# xmega.net
KiCad netlist of a schematic drawn in Altium Designer
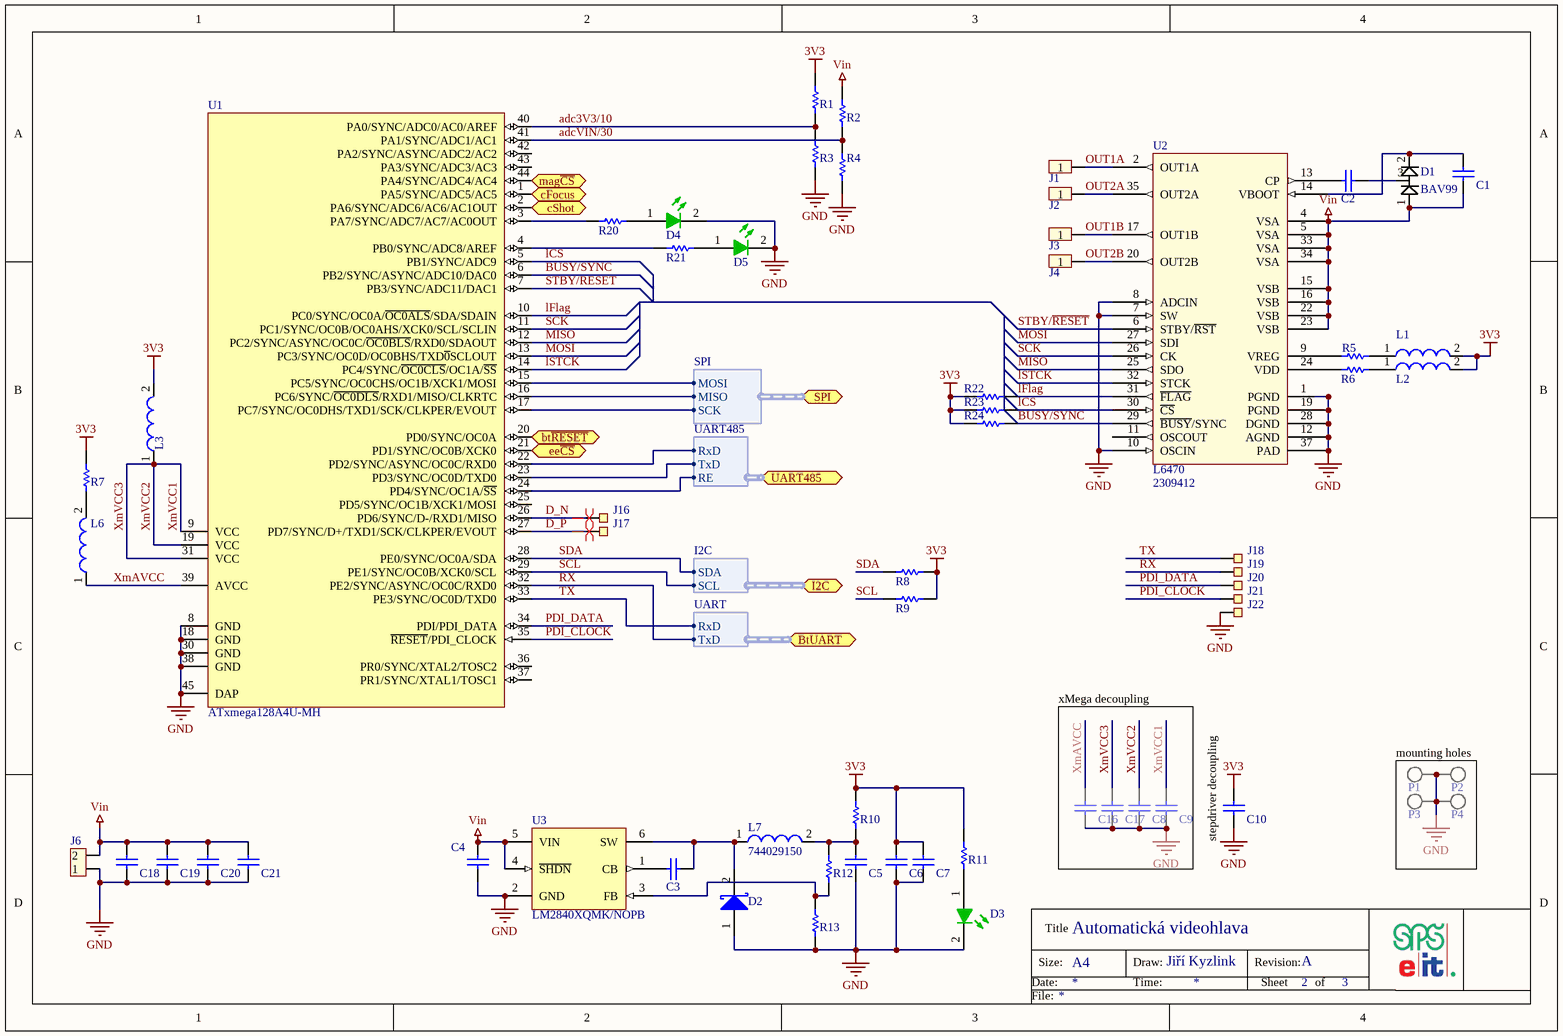
[diagram p0: xmega.SchDoc]

(export (version "E")
  (design (tool "Eeschema 10.0.6"))
  (components
    (comp (ref "C1")
      (value "CAP 220nF 50V 0603(1608)")
      (footprint "CAPC0603(1608)100_L")
      (description "CAP 220nF 50V ±20% 0603 (1608 Metric) Thickness 1mm SMD")
      (fields (field (name "TOLERANCE") "±20%"))
      (libsource (lib "Altium Content Vault") (part "CAP"))
    )
    (comp (ref "C2")
      (value "CAP 10nF 16V 0402(1005)")
      (footprint "CAPC0402(1005)60_L")
      (description "CAP 10nF 16V ±10% 0402 (1005 Metric) Thickness 0.6mm SMD")
      (fields (field (name "TOLERANCE") "±10%"))
      (libsource (lib "Altium Content Vault") (part "CAP"))
    )
    (comp (ref "C3")
      (value "CAP 100nF 16V 0402(1005)")
      (footprint "CAPC0402(1005)60_L")
      (description "CAP 100nF 16V ±10% 0402 (1005 Metric) Thickness 0.6mm SMD")
      (fields (field (name "TOLERANCE") "±10%"))
      (libsource (lib "Altium Content Vault") (part "CMP-1034-02069-1"))
    )
    (comp (ref "C4")
      (value "CAP 2.2pF 50V 0402(1005)")
      (footprint "CAPC0402(1005)60_L")
      (description "CAP 2.2pF 50V ±2% 0402 (1005 Metric) Thickness 0.6mm SMD")
      (fields (field (name "TOLERANCE") "±2%"))
      (libsource (lib "Altium Content Vault") (part "CAP"))
    )
    (comp (ref "C5")
      (value "CAP 10uF 6.3V 0402(1005)")
      (footprint "CAPC0402(1005)60_L")
      (description "CAP 10uF 6.3V ±20% 0402 (1005 Metric) Thickness 0.6mm SMD")
      (fields (field (name "TOLERANCE") "±20%"))
      (libsource (lib "Altium Content Vault") (part "CAP"))
    )
    (comp (ref "C6")
      (value "CAP 10uF 6.3V 0402(1005)")
      (footprint "CAPC0402(1005)60_L")
      (description "CAP 10uF 6.3V ±20% 0402 (1005 Metric) Thickness 0.6mm SMD")
      (fields (field (name "TOLERANCE") "±20%"))
      (libsource (lib "Altium Content Vault") (part "CAP"))
    )
    (comp (ref "C7")
      (value "CAP 10uF 6.3V 0402(1005)")
      (footprint "CAPC0402(1005)60_L")
      (description "CAP 10uF 6.3V ±20% 0402 (1005 Metric) Thickness 0.6mm SMD")
      (fields (field (name "TOLERANCE") "±20%"))
      (libsource (lib "Altium Content Vault") (part "CAP"))
    )
    (comp (ref "C8")
      (value "CAP 100nF 6.3V 0402(1005)")
      (footprint "CAPC0402(1005)60_L")
      (description "CAP 100nF 6.3V ±5% 0402 (1005 Metric) Thickness 0.6mm SMD")
      (fields (field (name "TOLERANCE") "±5%"))
      (libsource (lib "Altium Content Vault") (part "CAP"))
    )
    (comp (ref "C9")
      (value "CAP 100nF 6.3V 0402(1005)")
      (footprint "CAPC0402(1005)60_L")
      (description "CAP 100nF 6.3V ±5% 0402 (1005 Metric) Thickness 0.6mm SMD")
      (fields (field (name "TOLERANCE") "±5%"))
      (libsource (lib "Altium Content Vault") (part "CAP"))
    )
    (comp (ref "C10")
      (value "CAP 100nF 6.3V 0402(1005)")
      (footprint "CAPC0402(1005)60_L")
      (description "CAP 100nF 6.3V ±5% 0402 (1005 Metric) Thickness 0.6mm SMD")
      (fields (field (name "TOLERANCE") "±5%"))
      (libsource (lib "Altium Content Vault") (part "CAP"))
    )
    (comp (ref "C16")
      (value "CAP 100nF 16V 0402(1005)")
      (footprint "CAPC0402(1005)60_L")
      (description "CAP 100nF 16V ±10% 0402 (1005 Metric) Thickness 0.6mm SMD")
      (fields (field (name "TOLERANCE") "±10%"))
      (libsource (lib "Altium Content Vault") (part "CMP-1034-02069-1"))
    )
    (comp (ref "C17")
      (value "CAP 100nF 6.3V 0402(1005)")
      (footprint "CAPC0402(1005)60_L")
      (description "CAP 100nF 6.3V ±5% 0402 (1005 Metric) Thickness 0.6mm SMD")
      (fields (field (name "TOLERANCE") "±5%"))
      (libsource (lib "Altium Content Vault") (part "CAP"))
    )
    (comp (ref "C18")
      (value "CAP 1uF 50V 0603(1608)")
      (footprint "CAPC0603(1608)100_L")
      (description "CAP 1uF 50V ±10% 0603 (1608 Metric) Thickness 1mm SMD")
      (fields (field (name "TOLERANCE") "±10%"))
      (libsource (lib "Altium Content Vault") (part "CAP"))
    )
    (comp (ref "C19")
      (value "CAP 1uF 50V 0603(1608)")
      (footprint "CAPC0603(1608)100_L")
      (description "CAP 1uF 50V ±10% 0603 (1608 Metric) Thickness 1mm SMD")
      (fields (field (name "TOLERANCE") "±10%"))
      (libsource (lib "Altium Content Vault") (part "CAP"))
    )
    (comp (ref "C20")
      (value "CAP 1uF 50V 0603(1608)")
      (footprint "CAPC0603(1608)100_L")
      (description "CAP 1uF 50V ±10% 0603 (1608 Metric) Thickness 1mm SMD")
      (fields (field (name "TOLERANCE") "±10%"))
      (libsource (lib "Altium Content Vault") (part "CAP"))
    )
    (comp (ref "C21")
      (value "CAP 1uF 50V 0603(1608)")
      (footprint "CAPC0603(1608)100_L")
      (description "CAP 1uF 50V ±10% 0603 (1608 Metric) Thickness 1mm SMD")
      (fields (field (name "TOLERANCE") "±10%"))
      (libsource (lib "Altium Content Vault") (part "CAP"))
    )
    (comp (ref "D1")
      (value "BAV99")
      (footprint "MCHP-SOT-23-NB3_N")
      (libsource (lib "mojeLib") (part "BAV99"))
    )
    (comp (ref "D2")
      (value "ZHCS400")
      (footprint "DIOD-SOD323-2_V")
      (description "Schottky Diode, 400mA")
      (fields (field (name "MANUFACTURER") "Diodes Inc"))
      (libsource (lib "Altium Content Vault") (part "DIOD-DSKY-A1K2-2"))
    )
    (comp (ref "D3")
      (value "KP-1608MGC")
      (footprint "KING-0603LED_GREEN_V")
      (description "LED, SMT, 0603(1608), 1.1mm thickness, Green")
      (fields (field (name "MANUFACTURER") "Kingbright"))
      (libsource (lib "Altium Content Vault") (part "CMP-0404-00001-1"))
    )
    (comp (ref "D4")
      (value "KP-1608MGC")
      (footprint "KING-0603LED_GREEN_V")
      (description "LED, SMT, 0603(1608), 1.1mm thickness, Green")
      (fields (field (name "MANUFACTURER") "Kingbright"))
      (libsource (lib "Altium Content Vault") (part "CMP-0404-00001-1"))
    )
    (comp (ref "D5")
      (value "KP-1608MGC")
      (footprint "KING-0603LED_GREEN_V")
      (description "LED, SMT, 0603(1608), 1.1mm thickness, Green")
      (fields (field (name "MANUFACTURER") "Kingbright"))
      (libsource (lib "Altium Content Vault") (part "CMP-0404-00001-1"))
    )
    (comp (ref "J1") (value "Pin") (footprint "Hole 1mm") (libsource (lib "mojeLib") (part "Pin")))
    (comp (ref "J2") (value "Pin") (footprint "Hole 1mm") (libsource (lib "mojeLib") (part "Pin")))
    (comp (ref "J3") (value "Pin") (footprint "Hole 1mm") (libsource (lib "mojeLib") (part "Pin")))
    (comp (ref "J4") (value "Pin") (footprint "Hole 1mm") (libsource (lib "mojeLib") (part "Pin")))
    (comp (ref "J6")
      (value "jumper")
      (footprint "header 2pin")
      (libsource (lib "mojeLib") (part "header 2pin"))
    )
    (comp (ref "J16") (value "smd pad") (footprint "pad 0.75x1.5mm") (libsource (lib "mojeLib") (part "pad")))
    (comp (ref "J17") (value "smd pad") (footprint "pad 0.75x1.5mm") (libsource (lib "mojeLib") (part "pad")))
    (comp (ref "J18") (value "smd pad") (footprint "pad 0.75x1.5mm") (libsource (lib "mojeLib") (part "pad")))
    (comp (ref "J19") (value "smd pad") (footprint "pad 0.75x1.5mm") (libsource (lib "mojeLib") (part "pad")))
    (comp (ref "J20") (value "smd pad") (footprint "pad 0.75x1.5mm") (libsource (lib "mojeLib") (part "pad")))
    (comp (ref "J21") (value "smd pad") (footprint "pad 0.75x1.5mm") (libsource (lib "mojeLib") (part "pad")))
    (comp (ref "J22") (value "smd pad") (footprint "pad 0.75x1.5mm") (libsource (lib "mojeLib") (part "pad")))
    (comp (ref "L1")
      (value "742843122")
      (footprint "0402")
      (description "SMD EMI Suppression Ferrite Bead WE-CBF HF, Z = 220 Ohm")
      (libsource (lib "Altium Content Vault") (part "CMP-0220-00130-1"))
    )
    (comp (ref "L2")
      (value "742843122")
      (footprint "0402")
      (description "SMD EMI Suppression Ferrite Bead WE-CBF HF, Z = 220 Ohm")
      (libsource (lib "Altium Content Vault") (part "CMP-0220-00130-1"))
    )
    (comp (ref "L3")
      (value "742843122")
      (footprint "0402")
      (description "SMD EMI Suppression Ferrite Bead WE-CBF HF, Z = 220 Ohm")
      (libsource (lib "Altium Content Vault") (part "CMP-0220-00130-1"))
    )
    (comp (ref "L6")
      (value "742843122")
      (footprint "0402")
      (description "SMD EMI Suppression Ferrite Bead WE-CBF HF, Z = 220 Ohm")
      (libsource (lib "Altium Content Vault") (part "CMP-0220-00130-1"))
    )
    (comp (ref "L7")
      (value "744029150")
      (footprint "WE-TPC-2813-TH")
      (description "SMD Shielded Tiny Power Inductor WE-TPC, L = 15.0 µH")
      (libsource (lib "Altium Content Vault") (part "PAS-IND-INDUCTOR-2"))
    )
    (comp (ref "P1") (value "screw") (footprint "M3 screw") (libsource (lib "mojeLib") (part "screw")))
    (comp (ref "P2") (value "screw") (footprint "M3 screw") (libsource (lib "mojeLib") (part "screw")))
    (comp (ref "P3") (value "screw") (footprint "M3 screw") (libsource (lib "mojeLib") (part "screw")))
    (comp (ref "P4") (value "screw") (footprint "M3 screw") (libsource (lib "mojeLib") (part "screw")))
    (comp (ref "R1")
      (value "10K 1% 0402(1005)")
      (footprint "RESC0402(1005)_L")
      (description "10K 0.063W 1% 0402 (1005 Metric)  SMD")
      (fields (field (name "TOLERANCE") "1 %") (field (name "POWER") "0.063 W"))
      (libsource (lib "Altium Content Vault") (part "RES"))
    )
    (comp (ref "R2")
      (value "30K 1% 0402(1005)")
      (footprint "RESC0402(1005)_L")
      (description "30K 0.063W 1% 0402 (1005 Metric)  SMD")
      (fields (field (name "POWER") "0.063 W") (field (name "TOLERANCE") "1 %"))
      (libsource (lib "Altium Content Vault") (part "RES"))
    )
    (comp (ref "R3")
      (value "1K 1% 0402(1005)")
      (footprint "RESC0402(1005)_L")
      (description "1K 0.063W 1% 0402 (1005 Metric)  SMD")
      (fields (field (name "TOLERANCE") "1 %") (field (name "POWER") "0.063 W"))
      (libsource (lib "Altium Content Vault") (part "RES"))
    )
    (comp (ref "R4")
      (value "1K 1% 0402(1005)")
      (footprint "RESC0402(1005)_L")
      (description "1K 0.063W 1% 0402 (1005 Metric)  SMD")
      (fields (field (name "TOLERANCE") "1 %") (field (name "POWER") "0.063 W"))
      (libsource (lib "Altium Content Vault") (part "RES"))
    )
    (comp (ref "R5")
      (value "Jumper 0402(1005)")
      (footprint "RESC0402(1005)_L")
      (description "Jumper 0402 (1005 Metric)")
      (fields (field (name "TOLERANCE") "None"))
      (libsource (lib "Altium Content Vault") (part "CMP-1011-00001-1"))
    )
    (comp (ref "R6")
      (value "Jumper 0402(1005)")
      (footprint "RESC0402(1005)_L")
      (description "Jumper 0402 (1005 Metric)")
      (fields (field (name "TOLERANCE") "None"))
      (libsource (lib "Altium Content Vault") (part "CMP-1011-00001-1"))
    )
    (comp (ref "R7")
      (value "Jumper 0402(1005)")
      (footprint "RESC0402(1005)_L")
      (description "Jumper 0402 (1005 Metric)")
      (fields (field (name "TOLERANCE") "None"))
      (libsource (lib "Altium Content Vault") (part "RES"))
    )
    (comp (ref "R8")
      (value "4K7 1% 0402(1005)")
      (footprint "RESC0402(1005)_L")
      (description "4K7 0.063W 1% 0402 (1005 Metric)  SMD")
      (fields (field (name "POWER") "0.063 W") (field (name "TOLERANCE") "1 %"))
      (libsource (lib "Altium Content Vault") (part "RES"))
    )
    (comp (ref "R9")
      (value "4K7 1% 0402(1005)")
      (footprint "RESC0402(1005)_L")
      (description "4K7 0.063W 1% 0402 (1005 Metric)  SMD")
      (fields (field (name "POWER") "0.063 W") (field (name "TOLERANCE") "1 %"))
      (libsource (lib "Altium Content Vault") (part "CMP-1011-00586-1"))
    )
    (comp (ref "R10")
      (value "Jumper 0402(1005)")
      (footprint "RESC0402(1005)_L")
      (description "Jumper 0402 (1005 Metric)")
      (fields (field (name "TOLERANCE") "None"))
      (libsource (lib "Altium Content Vault") (part "RES"))
    )
    (comp (ref "R11")
      (value "130R 5% 0402(1005)")
      (footprint "RESC0402(1005)_L")
      (description "130R 0.063W 5% 0402 (1005 Metric)  SMD")
      (fields (field (name "POWER") "0.063 W") (field (name "TOLERANCE") "5 %"))
      (libsource (lib "Altium Content Vault") (part "RES"))
    )
    (comp (ref "R12")
      (value "1K02 1% 0402(1005)")
      (footprint "RESC0402(1005)_L")
      (description "1K02 0.063W 1% 0402 (1005 Metric)  SMD")
      (fields (field (name "TOLERANCE") "1 %") (field (name "POWER") "0.063 W"))
      (libsource (lib "Altium Content Vault") (part "RES"))
    )
    (comp (ref "R13")
      (value "3K4 1% 0402(1005)")
      (footprint "RESC0402(1005)_L")
      (description "3K4 0.063W 1% 0402 (1005 Metric)  SMD")
      (fields (field (name "TOLERANCE") "1 %") (field (name "POWER") "0.063 W"))
      (libsource (lib "Altium Content Vault") (part "RES"))
    )
    (comp (ref "R20")
      (value "130R 5% 0402(1005)")
      (footprint "RESC0402(1005)_L")
      (description "130R 0.063W 5% 0402 (1005 Metric)  SMD")
      (fields (field (name "POWER") "0.063 W") (field (name "TOLERANCE") "5 %"))
      (libsource (lib "Altium Content Vault") (part "CMP-1011-00053-1"))
    )
    (comp (ref "R21")
      (value "130R 5% 0402(1005)")
      (footprint "RESC0402(1005)_L")
      (description "130R 0.063W 5% 0402 (1005 Metric)  SMD")
      (fields (field (name "POWER") "0.063 W") (field (name "TOLERANCE") "5 %"))
      (libsource (lib "Altium Content Vault") (part "CMP-1011-00053-1"))
    )
    (comp (ref "R22")
      (value "39K 5% 0402(1005)")
      (footprint "RESC0402(1005)_L")
      (description "39K 0.063W 5% 0402 (1005 Metric)  SMD")
      (fields (field (name "TOLERANCE") "5 %") (field (name "POWER") "0.063 W"))
      (libsource (lib "Altium Content Vault") (part "RES"))
    )
    (comp (ref "R23")
      (value "39K 5% 0402(1005)")
      (footprint "RESC0402(1005)_L")
      (description "39K 0.063W 5% 0402 (1005 Metric)  SMD")
      (fields (field (name "TOLERANCE") "5 %") (field (name "POWER") "0.063 W"))
      (libsource (lib "Altium Content Vault") (part "RES"))
    )
    (comp (ref "R24")
      (value "39K 5% 0402(1005)")
      (footprint "RESC0402(1005)_L")
      (description "39K 0.063W 5% 0402 (1005 Metric)  SMD")
      (fields (field (name "TOLERANCE") "5 %") (field (name "POWER") "0.063 W"))
      (libsource (lib "Altium Content Vault") (part "RES"))
    )
    (comp (ref "U1")
      (value "ATxmega128A4U-MH")
      (footprint "qfn 44pin")
      (fields (field (name "MANUFACTURER") "Atmel"))
      (libsource (lib "Altium Content Vault") (part "CMP-0094-00056-2"))
    )
    (comp (ref "U2")
      (value "L6470")
      (footprint "POWERSO36")
      (fields (field (name "SUPPLIER PART NUMBER 1") "2309412"))
      (libsource (lib "mojeLib") (part "L6470"))
    )
    (comp (ref "U3")
      (value "LM2840XQMK/NOPB")
      (footprint "MK06A_N")
      (fields (field (name "MANUFACTURER") "National Semiconductor"))
      (libsource (lib "Altium Content Vault") (part "PM-DCDC-LM2841-6"))
    )
  )
  (nets
    (net (code "5") (name "/BUSY{slash}~{SYNC}") (class "Default")
      (node (ref "R24") (pin "2") (pinfunction "2_2") (pintype "passive"))
      (node (ref "U1") (pin "6") (pinfunction "PB2/SYNC/ASYNC/ADC10/DAC0_6") (pintype "bidirectional"))
      (node (ref "U2") (pin "29") (pinfunction "~{BUSY}/SYNC_29") (pintype "output"))
    )
    (net (code "6") (name "/D_N") (class "Default")
      (node (ref "J16") (pin "0") (pinfunction "0_0") (pintype "passive"))
      (node (ref "U1") (pin "26") (pinfunction "PD6/SYNC/D-/RXD1/MISO_26") (pintype "bidirectional"))
    )
    (net (code "7") (name "/D_P") (class "Default")
      (node (ref "J17") (pin "0") (pinfunction "0_0") (pintype "passive"))
      (node (ref "U1") (pin "27") (pinfunction "PD7/SYNC/D+/TXD1/SCK/CLKPER/EVOUT_27") (pintype "bidirectional"))
    )
    (net (code "8") (name "/MISO") (class "Default")
      (node (ref "U1") (pin "12") (pinfunction "PC2/SYNC/ASYNC/OC0C/~{OC0BLS}/RXD0/SDAOUT_12") (pintype "bidirectional"))
      (node (ref "U2") (pin "25") (pinfunction "SDO_25") (pintype "output"))
    )
    (net (code "9") (name "/MOSI") (class "Default")
      (node (ref "U1") (pin "13") (pinfunction "PC3/SYNC/OC0D/OC0BHS/TXD~{0}SCLOUT_13") (pintype "bidirectional"))
      (node (ref "U2") (pin "27") (pinfunction "SDI_27") (pintype "input"))
    )
    (net (code "10") (name "/OUT1A") (class "Default")
      (node (ref "J1") (pin "1") (pinfunction "1_1") (pintype "passive"))
      (node (ref "U2") (pin "2") (pinfunction "OUT1A_2") (pintype "output"))
    )
    (net (code "11") (name "/OUT1B") (class "Default")
      (node (ref "J3") (pin "1") (pinfunction "1_1") (pintype "passive"))
      (node (ref "U2") (pin "17") (pinfunction "OUT1B_17") (pintype "output"))
    )
    (net (code "12") (name "/OUT2A") (class "Default")
      (node (ref "J2") (pin "1") (pinfunction "1_1") (pintype "passive"))
      (node (ref "U2") (pin "35") (pinfunction "OUT2A_35") (pintype "output"))
    )
    (net (code "13") (name "/OUT2B") (class "Default")
      (node (ref "J4") (pin "1") (pinfunction "1_1") (pintype "passive"))
      (node (ref "U2") (pin "20") (pinfunction "OUT2B_20") (pintype "output"))
    )
    (net (code "14") (name "/PDI_CLOCK") (class "Default")
      (node (ref "J21") (pin "0") (pinfunction "0_0") (pintype "passive"))
      (node (ref "U1") (pin "35") (pinfunction "~{RESET}/PDI_CLOCK_35") (pintype "input"))
    )
    (net (code "15") (name "/PDI_DATA") (class "Default")
      (node (ref "J20") (pin "0") (pinfunction "0_0") (pintype "passive"))
      (node (ref "U1") (pin "34") (pinfunction "PDI/PDI_DATA_34") (pintype "bidirectional"))
    )
    (net (code "16") (name "/RE") (class "Default")
      (node (ref "U1") (pin "24") (pinfunction "PD4/SYNC/OC1A/~{SS}_24") (pintype "bidirectional"))
    )
    (net (code "17") (name "/RX") (class "Default")
      (node (ref "J19") (pin "0") (pinfunction "0_0") (pintype "passive"))
      (node (ref "U1") (pin "32") (pinfunction "PE2/SYNC/ASYNC/OC0C/RXD0_32") (pintype "bidirectional"))
    )
    (net (code "18") (name "/SCK") (class "Default")
      (node (ref "U1") (pin "11") (pinfunction "PC1/SYNC/OC0B/OC0AHS/XCK0/SCL/SCLIN_11") (pintype "bidirectional"))
      (node (ref "U2") (pin "26") (pinfunction "CK_26") (pintype "input"))
    )
    (net (code "19") (name "/SCL") (class "Default")
      (node (ref "R9") (pin "2") (pinfunction "2_2") (pintype "passive"))
      (node (ref "U1") (pin "29") (pinfunction "PE1/SYNC/OC0B/XCK0/SCL_29") (pintype "bidirectional"))
    )
    (net (code "20") (name "/SDA") (class "Default")
      (node (ref "R8") (pin "1") (pinfunction "1_1") (pintype "passive"))
      (node (ref "U1") (pin "28") (pinfunction "PE0/SYNC/OC0A/SDA_28") (pintype "bidirectional"))
    )
    (net (code "21") (name "/STBY{slash}~{RESET}") (class "Default")
      (node (ref "U1") (pin "7") (pinfunction "PB3/SYNC/ADC11/DAC1_7") (pintype "bidirectional"))
      (node (ref "U2") (pin "6") (pinfunction "STBY/~{RST}_6") (pintype "input"))
    )
    (net (code "22") (name "/TX") (class "Default")
      (node (ref "J18") (pin "0") (pinfunction "0_0") (pintype "passive"))
      (node (ref "U1") (pin "33") (pinfunction "PE3/SYNC/OC0D/TXD0_33") (pintype "bidirectional"))
    )
    (net (code "23") (name "/XmAVCC") (class "Default")
      (node (ref "C16") (pin "1") (pinfunction "1_1") (pintype "passive"))
      (node (ref "L6") (pin "1") (pinfunction "1_1") (pintype "passive"))
      (node (ref "U1") (pin "39") (pinfunction "AVCC_39") (pintype "power_in"))
    )
    (net (code "24") (name "/XmVCC1") (class "Default")
      (node (ref "C17") (pin "1") (pinfunction "1_1") (pintype "passive"))
      (node (ref "C8") (pin "1") (pinfunction "1_1") (pintype "passive"))
      (node (ref "C9") (pin "1") (pinfunction "1_1") (pintype "passive"))
      (node (ref "L3") (pin "1") (pinfunction "1_1") (pintype "passive"))
      (node (ref "U1") (pin "19") (pinfunction "VCC_19") (pintype "power_in"))
      (node (ref "U1") (pin "31") (pinfunction "VCC_31") (pintype "power_in"))
      (node (ref "U1") (pin "9") (pinfunction "VCC_9") (pintype "power_in"))
    )
    (net (code "25") (name "/adc3V3{slash}10") (class "Default")
      (node (ref "R1") (pin "1") (pinfunction "1_1") (pintype "passive"))
      (node (ref "R3") (pin "1") (pinfunction "1_1") (pintype "passive"))
      (node (ref "U1") (pin "40") (pinfunction "PA0/SYNC/ADC0/AC0/AREF_40") (pintype "bidirectional"))
    )
    (net (code "26") (name "/adcVIN{slash}30") (class "Default")
      (node (ref "R2") (pin "1") (pinfunction "1_1") (pintype "passive"))
      (node (ref "R4") (pin "1") (pinfunction "1_1") (pintype "passive"))
      (node (ref "U1") (pin "41") (pinfunction "PA1/SYNC/ADC1/AC1_41") (pintype "bidirectional"))
    )
    (net (code "27") (name "/bt~{RESET}") (class "Default")
      (node (ref "U1") (pin "20") (pinfunction "PD0/SYNC/OC0A_20") (pintype "bidirectional"))
    )
    (net (code "28") (name "/cFocus") (class "Default")
      (node (ref "U1") (pin "1") (pinfunction "PA5/SYNC/ADC5/AC5_1") (pintype "bidirectional"))
    )
    (net (code "29") (name "/cShot") (class "Default")
      (node (ref "U1") (pin "2") (pinfunction "PA6/SYNC/ADC6/AC6/AC1OUT_2") (pintype "bidirectional"))
    )
    (net (code "30") (name "/ee~{CS}") (class "Default")
      (node (ref "U1") (pin "21") (pinfunction "PD1/SYNC/OC0B/XCK0_21") (pintype "bidirectional"))
    )
    (net (code "31") (name "/lCS") (class "Default")
      (node (ref "R23") (pin "2") (pinfunction "2_2") (pintype "passive"))
      (node (ref "U1") (pin "5") (pinfunction "PB1/SYNC/ADC9_5") (pintype "bidirectional"))
      (node (ref "U2") (pin "30") (pinfunction "~{CS}_30") (pintype "input"))
    )
    (net (code "32") (name "/lFlag") (class "Default")
      (node (ref "R22") (pin "2") (pinfunction "2_2") (pintype "passive"))
      (node (ref "U1") (pin "10") (pinfunction "PC0/SYNC/OC0A/~{OC0ALS}/SDA/SDAIN_10") (pintype "bidirectional"))
      (node (ref "U2") (pin "31") (pinfunction "~{FLAG}_31") (pintype "output"))
    )
    (net (code "33") (name "/lSTCK") (class "Default")
      (node (ref "U1") (pin "14") (pinfunction "PC4/SYNC/~{OC0CLS}/OC1A/~{SS}_14") (pintype "bidirectional"))
      (node (ref "U2") (pin "32") (pinfunction "STCK_32") (pintype "input"))
    )
    (net (code "34") (name "/mag~{CS}") (class "Default")
      (node (ref "U1") (pin "44") (pinfunction "PA4/SYNC/ADC4/AC4_44") (pintype "bidirectional"))
    )
    (net (code "39") (name "3V3") (class "Default")
      (node (ref "C10") (pin "1") (pinfunction "1_1") (pintype "passive"))
      (node (ref "C6") (pin "2") (pinfunction "2_2") (pintype "passive"))
      (node (ref "C7") (pin "2") (pinfunction "2_2") (pintype "passive"))
      (node (ref "L1") (pin "2") (pinfunction "2_2") (pintype "passive"))
      (node (ref "L2") (pin "2") (pinfunction "2_2") (pintype "passive"))
      (node (ref "L3") (pin "2") (pinfunction "2_2") (pintype "passive"))
      (node (ref "R1") (pin "2") (pinfunction "2_2") (pintype "passive"))
      (node (ref "R10") (pin "2") (pinfunction "2_2") (pintype "passive"))
      (node (ref "R11") (pin "2") (pinfunction "2_2") (pintype "passive"))
      (node (ref "R22") (pin "1") (pinfunction "1_1") (pintype "passive"))
      (node (ref "R23") (pin "1") (pinfunction "1_1") (pintype "passive"))
      (node (ref "R24") (pin "1") (pinfunction "1_1") (pintype "passive"))
      (node (ref "R7") (pin "2") (pinfunction "2_2") (pintype "passive"))
      (node (ref "R8") (pin "2") (pinfunction "2_2") (pintype "passive"))
      (node (ref "R9") (pin "1") (pinfunction "1_1") (pintype "passive"))
    )
    (net (code "40") (name "GND") (class "Default")
      (node (ref "C10") (pin "2") (pinfunction "2_2") (pintype "passive"))
      (node (ref "C16") (pin "2") (pinfunction "2_2") (pintype "passive"))
      (node (ref "C17") (pin "2") (pinfunction "2_2") (pintype "passive"))
      (node (ref "C18") (pin "1") (pinfunction "1_1") (pintype "passive"))
      (node (ref "C19") (pin "1") (pinfunction "1_1") (pintype "passive"))
      (node (ref "C20") (pin "1") (pinfunction "1_1") (pintype "passive"))
      (node (ref "C21") (pin "1") (pinfunction "1_1") (pintype "passive"))
      (node (ref "C4") (pin "1") (pinfunction "1_1") (pintype "passive"))
      (node (ref "C5") (pin "1") (pinfunction "1_1") (pintype "passive"))
      (node (ref "C6") (pin "1") (pinfunction "1_1") (pintype "passive"))
      (node (ref "C7") (pin "1") (pinfunction "1_1") (pintype "passive"))
      (node (ref "C8") (pin "2") (pinfunction "2_2") (pintype "passive"))
      (node (ref "C9") (pin "2") (pinfunction "2_2") (pintype "passive"))
      (node (ref "D2") (pin "1") (pinfunction "A_1") (pintype "passive"))
      (node (ref "D3") (pin "2") (pinfunction "K_2") (pintype "passive"))
      (node (ref "D4") (pin "2") (pinfunction "K_2") (pintype "passive"))
      (node (ref "D5") (pin "2") (pinfunction "K_2") (pintype "passive"))
      (node (ref "J22") (pin "0") (pinfunction "0_0") (pintype "passive"))
      (node (ref "J6") (pin "1") (pinfunction "1_1") (pintype "passive"))
      (node (ref "P1") (pin "0") (pinfunction "1_0") (pintype "passive"))
      (node (ref "P2") (pin "0") (pinfunction "1_0") (pintype "passive"))
      (node (ref "P3") (pin "0") (pinfunction "1_0") (pintype "passive"))
      (node (ref "P4") (pin "0") (pinfunction "1_0") (pintype "passive"))
      (node (ref "R13") (pin "1") (pinfunction "1_1") (pintype "passive"))
      (node (ref "R3") (pin "2") (pinfunction "2_2") (pintype "passive"))
      (node (ref "R4") (pin "2") (pinfunction "2_2") (pintype "passive"))
      (node (ref "U1") (pin "18") (pinfunction "GND_18") (pintype "power_in"))
      (node (ref "U1") (pin "30") (pinfunction "GND_30") (pintype "power_in"))
      (node (ref "U1") (pin "38") (pinfunction "GND_38") (pintype "power_in"))
      (node (ref "U1") (pin "45") (pinfunction "DAP_45") (pintype "power_in"))
      (node (ref "U1") (pin "8") (pinfunction "GND_8") (pintype "power_in"))
      (node (ref "U2") (pin "1") (pinfunction "PGND_1") (pintype "power_in"))
      (node (ref "U2") (pin "10") (pinfunction "OSCIN_10") (pintype "input"))
      (node (ref "U2") (pin "12") (pinfunction "AGND_12") (pintype "power_in"))
      (node (ref "U2") (pin "19") (pinfunction "PGND_19") (pintype "power_in"))
      (node (ref "U2") (pin "28") (pinfunction "DGND_28") (pintype "power_in"))
      (node (ref "U2") (pin "37") (pinfunction "PAD_37") (pintype "passive"))
      (node (ref "U2") (pin "7") (pinfunction "SW_7") (pintype "input"))
      (node (ref "U2") (pin "8") (pinfunction "ADCIN_8") (pintype "input"))
      (node (ref "U3") (pin "2") (pinfunction "GND_2") (pintype "power_in"))
    )
    (net (code "41") (name "Net-(C2-Pad2)") (class "Default")
      (node (ref "C2") (pin "2") (pinfunction "2_2") (pintype "passive"))
      (node (ref "D1") (pin "3") (pinfunction "3_3") (pintype "passive"))
    )
    (net (code "42") (name "Net-(C5-Pad2)") (class "Default")
      (node (ref "C5") (pin "2") (pinfunction "2_2") (pintype "passive"))
      (node (ref "L7") (pin "2") (pinfunction "2_2") (pintype "passive"))
      (node (ref "R10") (pin "1") (pinfunction "1_1") (pintype "passive"))
      (node (ref "R12") (pin "2") (pinfunction "2_2") (pintype "passive"))
    )
    (net (code "43") (name "Net-(D2-K)") (class "Default")
      (node (ref "C3") (pin "2") (pinfunction "2_2") (pintype "passive"))
      (node (ref "D2") (pin "2") (pinfunction "K_2") (pintype "passive"))
      (node (ref "L7") (pin "1") (pinfunction "1_1") (pintype "passive"))
      (node (ref "U3") (pin "6") (pinfunction "SW_6") (pintype "power_in"))
    )
    (net (code "44") (name "Net-(D3-A)") (class "Default")
      (node (ref "D3") (pin "1") (pinfunction "A_1") (pintype "passive"))
      (node (ref "R11") (pin "1") (pinfunction "1_1") (pintype "passive"))
    )
    (net (code "45") (name "Net-(D4-A)") (class "Default")
      (node (ref "D4") (pin "1") (pinfunction "A_1") (pintype "passive"))
      (node (ref "R20") (pin "2") (pinfunction "2_2") (pintype "passive"))
    )
    (net (code "46") (name "Net-(D5-A)") (class "Default")
      (node (ref "D5") (pin "1") (pinfunction "A_1") (pintype "passive"))
      (node (ref "R21") (pin "2") (pinfunction "2_2") (pintype "passive"))
    )
    (net (code "47") (name "Net-(L1-Pad1)") (class "Default")
      (node (ref "L1") (pin "1") (pinfunction "1_1") (pintype "passive"))
      (node (ref "R5") (pin "2") (pinfunction "2_2") (pintype "passive"))
    )
    (net (code "48") (name "Net-(L2-Pad1)") (class "Default")
      (node (ref "L2") (pin "1") (pinfunction "1_1") (pintype "passive"))
      (node (ref "R6") (pin "2") (pinfunction "2_2") (pintype "passive"))
    )
    (net (code "49") (name "Net-(L6-Pad2)") (class "Default")
      (node (ref "L6") (pin "2") (pinfunction "2_2") (pintype "passive"))
      (node (ref "R7") (pin "1") (pinfunction "1_1") (pintype "passive"))
    )
    (net (code "50") (name "Net-(U1-PA7{slash}SYNC{slash}ADC7{slash}AC7{slash}AC0OUT)") (class "Default")
      (node (ref "R20") (pin "1") (pinfunction "1_1") (pintype "passive"))
      (node (ref "U1") (pin "3") (pinfunction "PA7/SYNC/ADC7/AC7/AC0OUT_3") (pintype "bidirectional"))
    )
    (net (code "51") (name "Net-(U1-PB0{slash}SYNC{slash}ADC8{slash}AREF)") (class "Default")
      (node (ref "R21") (pin "1") (pinfunction "1_1") (pintype "passive"))
      (node (ref "U1") (pin "4") (pinfunction "PB0/SYNC/ADC8/AREF_4") (pintype "bidirectional"))
    )
    (net (code "52") (name "Net-(U2-CP)") (class "Default")
      (node (ref "C2") (pin "1") (pinfunction "1_1") (pintype "passive"))
      (node (ref "U2") (pin "13") (pinfunction "CP_13") (pintype "output"))
    )
    (net (code "53") (name "Net-(U2-VBOOT)") (class "Default")
      (node (ref "C1") (pin "2") (pinfunction "2_2") (pintype "passive"))
      (node (ref "D1") (pin "2") (pinfunction "2_2") (pintype "passive"))
      (node (ref "U2") (pin "14") (pinfunction "VBOOT_14") (pintype "input"))
    )
    (net (code "54") (name "Net-(U2-VDD)") (class "Default")
      (node (ref "R6") (pin "1") (pinfunction "1_1") (pintype "passive"))
      (node (ref "U2") (pin "24") (pinfunction "VDD_24") (pintype "power_in"))
    )
    (net (code "55") (name "Net-(U2-VREG)") (class "Default")
      (node (ref "R5") (pin "1") (pinfunction "1_1") (pintype "passive"))
      (node (ref "U2") (pin "9") (pinfunction "VREG_9") (pintype "power_in"))
    )
    (net (code "56") (name "Net-(U3-CB)") (class "Default")
      (node (ref "C3") (pin "1") (pinfunction "1_1") (pintype "passive"))
      (node (ref "U3") (pin "1") (pinfunction "CB_1") (pintype "output"))
    )
    (net (code "57") (name "Net-(U3-FB)") (class "Default")
      (node (ref "R12") (pin "1") (pinfunction "1_1") (pintype "passive"))
      (node (ref "R13") (pin "2") (pinfunction "2_2") (pintype "passive"))
      (node (ref "U3") (pin "3") (pinfunction "FB_3") (pintype "input"))
    )
    (net (code "58") (name "Vin") (class "Default")
      (node (ref "C1") (pin "1") (pinfunction "1_1") (pintype "passive"))
      (node (ref "C18") (pin "2") (pinfunction "2_2") (pintype "passive"))
      (node (ref "C19") (pin "2") (pinfunction "2_2") (pintype "passive"))
      (node (ref "C20") (pin "2") (pinfunction "2_2") (pintype "passive"))
      (node (ref "C21") (pin "2") (pinfunction "2_2") (pintype "passive"))
      (node (ref "C4") (pin "2") (pinfunction "2_2") (pintype "passive"))
      (node (ref "D1") (pin "1") (pinfunction "1_1") (pintype "passive"))
      (node (ref "J6") (pin "2") (pinfunction "2_2") (pintype "passive"))
      (node (ref "R2") (pin "2") (pinfunction "2_2") (pintype "passive"))
      (node (ref "U2") (pin "15") (pinfunction "VSB_15") (pintype "power_in"))
      (node (ref "U2") (pin "16") (pinfunction "VSB_16") (pintype "power_in"))
      (node (ref "U2") (pin "22") (pinfunction "VSB_22") (pintype "power_in"))
      (node (ref "U2") (pin "23") (pinfunction "VSB_23") (pintype "power_in"))
      (node (ref "U2") (pin "33") (pinfunction "VSA_33") (pintype "power_in"))
      (node (ref "U2") (pin "34") (pinfunction "VSA_34") (pintype "power_in"))
      (node (ref "U2") (pin "4") (pinfunction "VSA_4") (pintype "power_in"))
      (node (ref "U2") (pin "5") (pinfunction "VSA_5") (pintype "power_in"))
      (node (ref "U3") (pin "4") (pinfunction "~{SHDN}_4") (pintype "input"))
      (node (ref "U3") (pin "5") (pinfunction "VIN_5") (pintype "power_in"))
    )
    (net (code "59") (name "unconnected-(U1-PA2{slash}SYNC{slash}ASYNC{slash}ADC2{slash}AC2-Pad42)") (class "Default")
      (node (ref "U1") (pin "42") (pinfunction "PA2/SYNC/ASYNC/ADC2/AC2_42") (pintype "bidirectional"))
    )
    (net (code "60") (name "unconnected-(U1-PA3{slash}SYNC{slash}ADC3{slash}AC3-Pad43)") (class "Default")
      (node (ref "U1") (pin "43") (pinfunction "PA3/SYNC/ADC3/AC3_43") (pintype "bidirectional"))
    )
    (net (code "61") (name "unconnected-(U1-PC5{slash}SYNC{slash}OC0CHS{slash}OC1B{slash}XCK1{slash}MOSI-Pad15)") (class "Default")
      (node (ref "U1") (pin "15") (pinfunction "PC5/SYNC/OC0CHS/OC1B/XCK1/MOSI_15") (pintype "bidirectional"))
    )
    (net (code "62") (name "unconnected-(U1-PC6{slash}SYNC{slash}~{OC0DLS}{slash}RXD1{slash}MISO{slash}CLKRTC-Pad16)") (class "Default")
      (node (ref "U1") (pin "16") (pinfunction "PC6/SYNC/~{OC0DLS}/RXD1/MISO/CLKRTC_16") (pintype "bidirectional"))
    )
    (net (code "63") (name "unconnected-(U1-PC7{slash}SYNC{slash}OC0DHS{slash}TXD1{slash}SCK{slash}CLKPER{slash}EVOUT-Pad17)") (class "Default")
      (node (ref "U1") (pin "17") (pinfunction "PC7/SYNC/OC0DHS/TXD1/SCK/CLKPER/EVOUT_17") (pintype "bidirectional"))
    )
    (net (code "64") (name "unconnected-(U1-PD2{slash}SYNC{slash}ASYNC{slash}OC0C{slash}RXD0-Pad22)") (class "Default")
      (node (ref "U1") (pin "22") (pinfunction "PD2/SYNC/ASYNC/OC0C/RXD0_22") (pintype "bidirectional"))
    )
    (net (code "65") (name "unconnected-(U1-PD3{slash}SYNC{slash}OC0D{slash}TXD0-Pad23)") (class "Default")
      (node (ref "U1") (pin "23") (pinfunction "PD3/SYNC/OC0D/TXD0_23") (pintype "bidirectional"))
    )
    (net (code "66") (name "unconnected-(U1-PD5{slash}SYNC{slash}OC1B{slash}XCK1{slash}MOSI-Pad25)") (class "Default")
      (node (ref "U1") (pin "25") (pinfunction "PD5/SYNC/OC1B/XCK1/MOSI_25") (pintype "bidirectional"))
    )
    (net (code "67") (name "unconnected-(U1-PR0{slash}SYNC{slash}XTAL2{slash}TOSC2-Pad36)") (class "Default")
      (node (ref "U1") (pin "36") (pinfunction "PR0/SYNC/XTAL2/TOSC2_36") (pintype "bidirectional"))
    )
    (net (code "68") (name "unconnected-(U1-PR1{slash}SYNC{slash}XTAL1{slash}TOSC1-Pad37)") (class "Default")
      (node (ref "U1") (pin "37") (pinfunction "PR1/SYNC/XTAL1/TOSC1_37") (pintype "bidirectional"))
    )
    (net (code "69") (name "unconnected-(U2-OSCOUT-Pad11)") (class "Default")
      (node (ref "U2") (pin "11") (pinfunction "OSCOUT_11") (pintype "output"))
    )
  )
)
